# mux_breakout.net
KiCad netlist of a schematic drawn in EAGLE
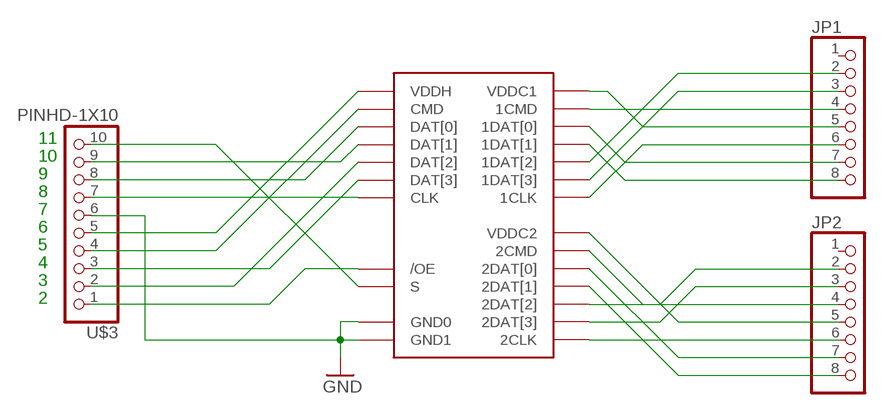
[diagram p0: schematic, sheet 1]

(export (version "E")
  (design (tool "Eeschema 10.0.6"))
  (components
    (comp (ref "JP1")
      (value "PINHD-1X8CLEANBIG")
      (footprint "eagle-import:1X08-CLEANBIG")
      (libsource (lib "eagle-import") (part "PINHD-1X8CLEANBIG"))
    )
    (comp (ref "JP2")
      (value "PINHD-1X8CLEANBIG")
      (footprint "eagle-import:1X08-CLEANBIG")
      (libsource (lib "eagle-import") (part "PINHD-1X8CLEANBIG"))
    )
    (comp (ref "U$1")
      (value "FSSD06")
      (footprint "eagle-import:MLP-24")
      (libsource (lib "eagle-import") (part "FSSD06"))
    )
    (comp (ref "U$3")
      (value "PINHD-1X10")
      (footprint "eagle-import:1X10-BIG")
      (libsource (lib "eagle-import") (part "PINHD-1X10"))
    )
  )
  (nets
    (net (code "1") (name "GND") (class "Default")
      (node (ref "U$1") (pin "GND0") (pinfunction "GND0_GND0") (pintype "bidirectional"))
      (node (ref "U$1") (pin "GND1") (pinfunction "GND1_GND1") (pintype "bidirectional"))
      (node (ref "U$3") (pin "6") (pinfunction "6_6") (pintype "passive"))
    )
    (net (code "2") (name "Net-(JP1-Pad2)") (class "Default")
      (node (ref "JP1") (pin "2") (pinfunction "2_2") (pintype "passive"))
      (node (ref "U$1") (pin "1DAT[2]") (pinfunction "1DAT[2]_1DAT[2]") (pintype "bidirectional"))
    )
    (net (code "3") (name "Net-(JP1-Pad3)") (class "Default")
      (node (ref "JP1") (pin "3") (pinfunction "3_3") (pintype "passive"))
      (node (ref "U$1") (pin "1DAT[3]") (pinfunction "1DAT[3]_1DAT[3]") (pintype "bidirectional"))
    )
    (net (code "4") (name "Net-(JP1-Pad4)") (class "Default")
      (node (ref "JP1") (pin "4") (pinfunction "4_4") (pintype "passive"))
      (node (ref "U$1") (pin "1CMD") (pinfunction "1CMD_1CMD") (pintype "bidirectional"))
    )
    (net (code "5") (name "Net-(JP1-Pad5)") (class "Default")
      (node (ref "JP1") (pin "5") (pinfunction "5_5") (pintype "passive"))
      (node (ref "U$1") (pin "VDDC1") (pinfunction "VDDC1_VDDC1") (pintype "bidirectional"))
    )
    (net (code "6") (name "Net-(JP1-Pad6)") (class "Default")
      (node (ref "JP1") (pin "6") (pinfunction "6_6") (pintype "passive"))
      (node (ref "U$1") (pin "1CLK") (pinfunction "1CLK_1CLK") (pintype "bidirectional"))
    )
    (net (code "7") (name "Net-(JP1-Pad7)") (class "Default")
      (node (ref "JP1") (pin "7") (pinfunction "7_7") (pintype "passive"))
      (node (ref "U$1") (pin "1DAT[0]") (pinfunction "1DAT[0]_1DAT[0]") (pintype "bidirectional"))
    )
    (net (code "8") (name "Net-(JP1-Pad8)") (class "Default")
      (node (ref "JP1") (pin "8") (pinfunction "8_8") (pintype "passive"))
      (node (ref "U$1") (pin "1DAT[1]") (pinfunction "1DAT[1]_1DAT[1]") (pintype "bidirectional"))
    )
    (net (code "9") (name "Net-(JP2-Pad2)") (class "Default")
      (node (ref "JP2") (pin "2") (pinfunction "2_2") (pintype "passive"))
      (node (ref "U$1") (pin "2DAT[2]") (pinfunction "2DAT[2]_2DAT[2]") (pintype "bidirectional"))
    )
    (net (code "10") (name "Net-(JP2-Pad3)") (class "Default")
      (node (ref "JP2") (pin "3") (pinfunction "3_3") (pintype "passive"))
      (node (ref "U$1") (pin "2DAT[3]") (pinfunction "2DAT[3]_2DAT[3]") (pintype "bidirectional"))
    )
    (net (code "11") (name "Net-(JP2-Pad4)") (class "Default")
      (node (ref "JP2") (pin "4") (pinfunction "4_4") (pintype "passive"))
      (node (ref "U$1") (pin "2CMD") (pinfunction "2CMD_2CMD") (pintype "bidirectional"))
    )
    (net (code "12") (name "Net-(JP2-Pad5)") (class "Default")
      (node (ref "JP2") (pin "5") (pinfunction "5_5") (pintype "passive"))
      (node (ref "U$1") (pin "VDDC2") (pinfunction "VDDC2_VDDC2") (pintype "bidirectional"))
    )
    (net (code "13") (name "Net-(JP2-Pad7)") (class "Default")
      (node (ref "JP2") (pin "7") (pinfunction "7_7") (pintype "passive"))
      (node (ref "U$1") (pin "2DAT[0]") (pinfunction "2DAT[0]_2DAT[0]") (pintype "bidirectional"))
    )
    (net (code "14") (name "Net-(JP2-Pad8)") (class "Default")
      (node (ref "JP2") (pin "8") (pinfunction "8_8") (pintype "passive"))
      (node (ref "U$1") (pin "2DAT[1]") (pinfunction "2DAT[1]_2DAT[1]") (pintype "bidirectional"))
    )
    (net (code "15") (name "Net-(U$1-2CLK)") (class "Default")
      (node (ref "JP2") (pin "6") (pinfunction "6_6") (pintype "passive"))
      (node (ref "U$1") (pin "2CLCK") (pinfunction "2CLK_2CLCK") (pintype "bidirectional"))
    )
    (net (code "16") (name "Net-(U$1-PadCLK)") (class "Default")
      (node (ref "U$1") (pin "CLK") (pinfunction "CLK_CLK") (pintype "bidirectional"))
      (node (ref "U$3") (pin "7") (pinfunction "7_7") (pintype "passive"))
    )
    (net (code "17") (name "Net-(U$1-PadCMD)") (class "Default")
      (node (ref "U$1") (pin "CMD") (pinfunction "CMD_CMD") (pintype "bidirectional"))
      (node (ref "U$3") (pin "4") (pinfunction "4_4") (pintype "passive"))
    )
    (net (code "18") (name "Net-(U$1-PadDAT[0])") (class "Default")
      (node (ref "U$1") (pin "DAT[0]") (pinfunction "DAT[0]_DAT[0]") (pintype "bidirectional"))
      (node (ref "U$3") (pin "8") (pinfunction "8_8") (pintype "passive"))
    )
    (net (code "19") (name "Net-(U$1-PadDAT[1])") (class "Default")
      (node (ref "U$1") (pin "DAT[1]") (pinfunction "DAT[1]_DAT[1]") (pintype "bidirectional"))
      (node (ref "U$3") (pin "9") (pinfunction "9_9") (pintype "passive"))
    )
    (net (code "20") (name "Net-(U$1-PadDAT[2])") (class "Default")
      (node (ref "U$1") (pin "DAT[2]") (pinfunction "DAT[2]_DAT[2]") (pintype "bidirectional"))
      (node (ref "U$3") (pin "2") (pinfunction "2_2") (pintype "passive"))
    )
    (net (code "21") (name "Net-(U$1-PadDAT[3])") (class "Default")
      (node (ref "U$1") (pin "DAT[3]") (pinfunction "DAT[3]_DAT[3]") (pintype "bidirectional"))
      (node (ref "U$3") (pin "3") (pinfunction "3_3") (pintype "passive"))
    )
    (net (code "22") (name "Net-(U$1-PadS)") (class "Default")
      (node (ref "U$1") (pin "S") (pinfunction "S_S") (pintype "bidirectional"))
      (node (ref "U$3") (pin "10") (pinfunction "10_10") (pintype "passive"))
    )
    (net (code "23") (name "Net-(U$1-PadVDDH)") (class "Default")
      (node (ref "U$1") (pin "VDDH") (pinfunction "VDDH_VDDH") (pintype "bidirectional"))
      (node (ref "U$3") (pin "5") (pinfunction "5_5") (pintype "passive"))
    )
    (net (code "24") (name "Net-(U$1-Pad{slash}OE)") (class "Default")
      (node (ref "U$1") (pin "/OE") (pinfunction "/OE_/OE") (pintype "bidirectional"))
      (node (ref "U$3") (pin "1") (pinfunction "1_1") (pintype "passive"))
    )
    (net (code "25") (name "unconnected-(JP1-Pad1)") (class "Default")
      (node (ref "JP1") (pin "1") (pinfunction "1_1") (pintype "passive"))
    )
    (net (code "26") (name "unconnected-(JP2-Pad1)") (class "Default")
      (node (ref "JP2") (pin "1") (pinfunction "1_1") (pintype "passive"))
    )
  )
)
